# Qwiic_GPS-TwoSided.net
KiCad netlist of a schematic drawn in EAGLE
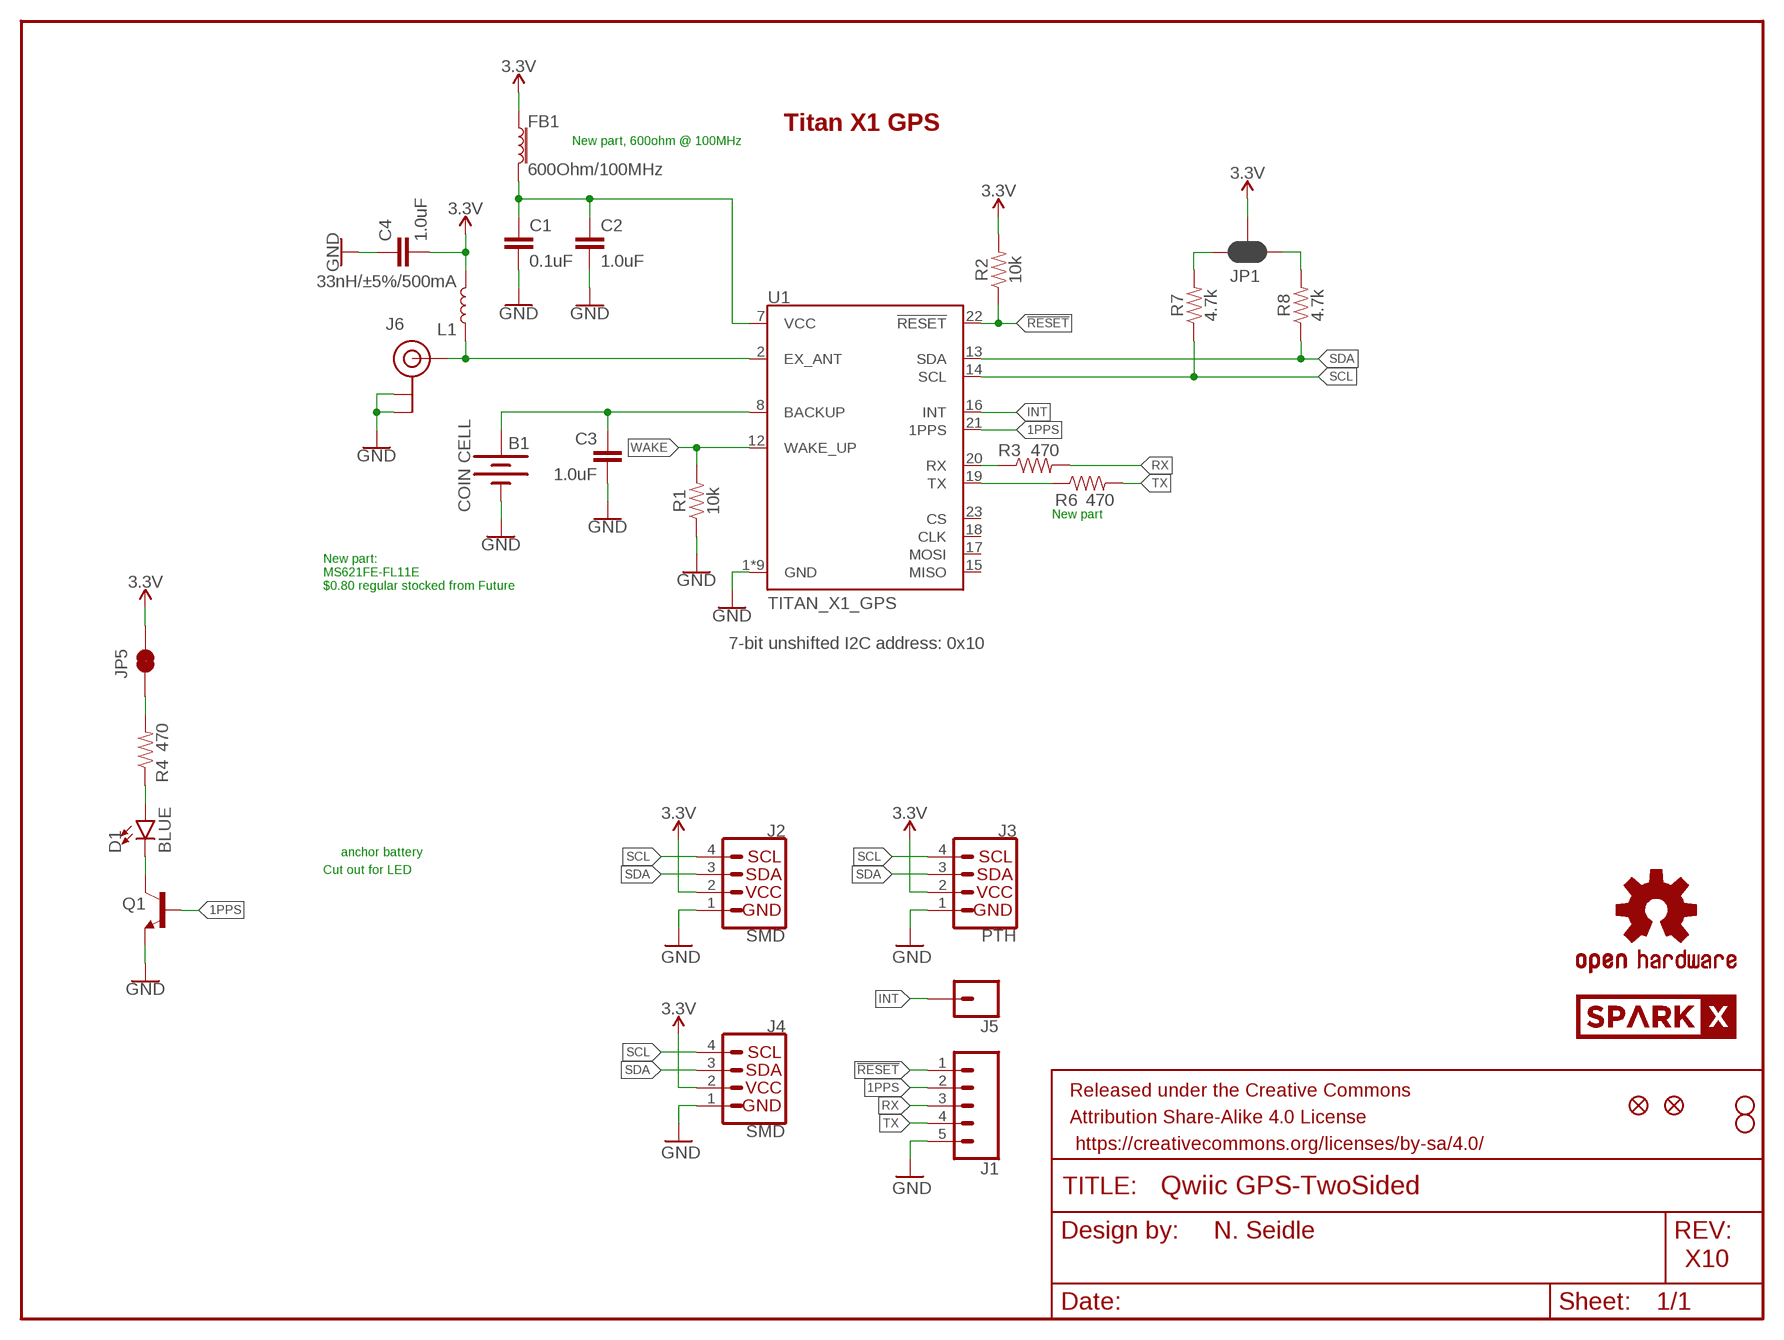
[diagram p0: schematic, sheet 1]

(export (version "E")
  (design (tool "Eeschema 10.0.6"))
  (components
    (comp (ref "B1")
      (value "COIN CELL")
      (footprint "eagle-import:6.8MM_COIN_CELL")
      (libsource (lib "eagle-import") (part "6.8MM_COIN_CELL"))
    )
    (comp (ref "C1")
      (value "0.1uF")
      (footprint "eagle-import:0603")
      (libsource (lib "eagle-import") (part "0.1UF-0603-25V-(+80/-20%)"))
    )
    (comp (ref "C2")
      (value "1.0uF")
      (footprint "eagle-import:0603")
      (libsource (lib "eagle-import") (part "1.0UF-0603-16V-10%"))
    )
    (comp (ref "C3")
      (value "1.0uF")
      (footprint "eagle-import:0603")
      (libsource (lib "eagle-import") (part "1.0UF-0603-16V-10%"))
    )
    (comp (ref "C4")
      (value "1.0uF")
      (footprint "eagle-import:0603")
      (libsource (lib "eagle-import") (part "1.0UF-0603-16V-10%"))
    )
    (comp (ref "D1")
      (value "BLUE")
      (footprint "eagle-import:LED-1206-BOTTOM")
      (libsource (lib "eagle-import") (part "LED1206-BOTTOM"))
    )
    (comp (ref "FB1")
      (value "600Ohm/100MHz")
      (footprint "eagle-import:0603")
      (libsource (lib "eagle-import") (part "FERRITE_BEAD-0603"))
    )
    (comp (ref "FRAME1")
      (value "FRAME-LETTER")
      (footprint "eagle-import:CREATIVE_COMMONS")
      (libsource (lib "eagle-import") (part "FRAME-LETTER"))
    )
    (comp (ref "J1")
      (value "CONN_05NO_SILK")
      (footprint "eagle-import:1X05_NO_SILK")
      (libsource (lib "eagle-import") (part "CONN_05NO_SILK"))
    )
    (comp (ref "J2")
      (value "SMD")
      (footprint "eagle-import:1X04_1MM_RA")
      (libsource (lib "eagle-import") (part "I2C_STANDARDJS-1MM"))
    )
    (comp (ref "J3")
      (value "PTH")
      (footprint "eagle-import:1X04_NO_SILK")
      (libsource (lib "eagle-import") (part "I2C_STANDARD_NO_SILK"))
    )
    (comp (ref "J4")
      (value "SMD")
      (footprint "eagle-import:1X04_1MM_RA")
      (libsource (lib "eagle-import") (part "I2C_STANDARDJS-1MM"))
    )
    (comp (ref "J5")
      (value "CONN_01PTH_NO_SILK_YES_STOP")
      (footprint "eagle-import:1X01_NO_SILK")
      (libsource (lib "eagle-import") (part "CONN_01PTH_NO_SILK_YES_STOP"))
    )
    (comp (ref "J6")
      (value "U.FL")
      (footprint "eagle-import:U.FL")
      (libsource (lib "eagle-import") (part "U.FL"))
    )
    (comp (ref "JP1")
      (value "JUMPER-SMT_3_2-NC_PASTE_SILK")
      (footprint "eagle-import:SMT-JUMPER_3_2-NC_PASTE_SILK")
      (libsource (lib "eagle-import") (part "JUMPER-SMT_3_2-NC_PASTE_SILK"))
    )
    (comp (ref "JP2")
      (value "FIDUCIALUFIDUCIAL")
      (footprint "eagle-import:MICRO-FIDUCIAL")
      (libsource (lib "eagle-import") (part "FIDUCIALUFIDUCIAL"))
    )
    (comp (ref "JP3")
      (value "STAND-OFF")
      (footprint "eagle-import:STAND-OFF")
      (libsource (lib "eagle-import") (part "STAND-OFF"))
    )
    (comp (ref "JP4")
      (value "STAND-OFF")
      (footprint "eagle-import:STAND-OFF")
      (libsource (lib "eagle-import") (part "STAND-OFF"))
    )
    (comp (ref "JP5")
      (value "JUMPER-SMT_2_NC_TRACE_NO-SILK")
      (footprint "eagle-import:SMT-JUMPER_2_NC_TRACE_NO-SILK")
      (libsource (lib "eagle-import") (part "JUMPER-SMT_2_NC_TRACE_NO-SILK"))
    )
    (comp (ref "JP6")
      (value "FIDUCIALUFIDUCIAL")
      (footprint "eagle-import:MICRO-FIDUCIAL")
      (libsource (lib "eagle-import") (part "FIDUCIALUFIDUCIAL"))
    )
    (comp (ref "L1")
      (value "33nH/±5%/500mA")
      (footprint "eagle-import:0603")
      (libsource (lib "eagle-import") (part "INDUCTOR-0603-33NH"))
    )
    (comp (ref "LOGO1")
      (value "OSHW-LOGOMINI")
      (footprint "eagle-import:OSHW-LOGO-MINI")
      (libsource (lib "eagle-import") (part "OSHW-LOGOMINI"))
    )
    (comp (ref "Q1")
      (value "TRANS_NPN-MMBT2222AL")
      (footprint "eagle-import:SOT23-3")
      (libsource (lib "eagle-import") (part "TRANS_NPN-MMBT2222AL"))
    )
    (comp (ref "R1")
      (value "10k")
      (footprint "eagle-import:0603")
      (libsource (lib "eagle-import") (part "10KOHM-0603-1/10W-1%"))
    )
    (comp (ref "R2")
      (value "10k")
      (footprint "eagle-import:0603")
      (libsource (lib "eagle-import") (part "10KOHM-0603-1/10W-1%"))
    )
    (comp (ref "R3")
      (value "470")
      (footprint "eagle-import:0603")
      (libsource (lib "eagle-import") (part "470OHM-0603-1/10W-1%"))
    )
    (comp (ref "R4")
      (value "470")
      (footprint "eagle-import:0603")
      (libsource (lib "eagle-import") (part "470OHM-0603-1/10W-1%"))
    )
    (comp (ref "R6")
      (value "470")
      (footprint "eagle-import:0603")
      (libsource (lib "eagle-import") (part "470OHM-0603-1/10W-1%"))
    )
    (comp (ref "R7")
      (value "4.7k")
      (footprint "eagle-import:0603")
      (libsource (lib "eagle-import") (part "4.7KOHM-0603-1/10W-1%"))
    )
    (comp (ref "R8")
      (value "4.7k")
      (footprint "eagle-import:0603")
      (libsource (lib "eagle-import") (part "4.7KOHM-0603-1/10W-1%"))
    )
    (comp (ref "U$1")
      (value "SPARKX-LOGO4")
      (footprint "eagle-import:SPARKX-MEDIUM")
      (libsource (lib "eagle-import") (part "SPARKX-LOGO4"))
    )
    (comp (ref "U$2")
      (value "SPARKX-LOGO4")
      (footprint "eagle-import:SPARKX-MEDIUM")
      (libsource (lib "eagle-import") (part "SPARKX-LOGO4"))
    )
    (comp (ref "U1")
      (value "TITAN_X1_GPS")
      (footprint "eagle-import:TITAN_X1_GPS")
      (libsource (lib "eagle-import") (part "TITAN_X1_GPS"))
    )
  )
  (nets
    (net (code "1") (name "/~{RESET}") (class "Default")
      (node (ref "J1") (pin "1") (pinfunction "1_1") (pintype "passive"))
      (node (ref "R2") (pin "1") (pinfunction "1_1") (pintype "passive"))
      (node (ref "U1") (pin "22") (pinfunction "~{RESET}_22") (pintype "bidirectional"))
    )
    (net (code "2") (name "1PPS") (class "Default")
      (node (ref "J1") (pin "2") (pinfunction "2_2") (pintype "passive"))
      (node (ref "Q1") (pin "1") (pinfunction "B_1") (pintype "passive"))
      (node (ref "U1") (pin "21") (pinfunction "1PPS_21") (pintype "bidirectional"))
    )
    (net (code "3") (name "3.3V") (class "Default")
      (node (ref "C4") (pin "2") (pinfunction "2_2") (pintype "passive"))
      (node (ref "FB1") (pin "1") (pinfunction "1_1") (pintype "passive"))
      (node (ref "J2") (pin "2") (pinfunction "VCC_2") (pintype "power_in"))
      (node (ref "J3") (pin "2") (pinfunction "VCC_2") (pintype "power_in"))
      (node (ref "J4") (pin "2") (pinfunction "VCC_2") (pintype "power_in"))
      (node (ref "JP1") (pin "2") (pinfunction "2_2") (pintype "passive"))
      (node (ref "JP5") (pin "2") (pinfunction "2_2") (pintype "passive"))
      (node (ref "L1") (pin "2") (pinfunction "2_2") (pintype "passive"))
      (node (ref "R2") (pin "2") (pinfunction "2_2") (pintype "passive"))
    )
    (net (code "4") (name "GND") (class "Default")
      (node (ref "B1") (pin "-") (pinfunction "-_-") (pintype "power_in"))
      (node (ref "C1") (pin "2") (pinfunction "2_2") (pintype "passive"))
      (node (ref "C2") (pin "2") (pinfunction "2_2") (pintype "passive"))
      (node (ref "C3") (pin "2") (pinfunction "2_2") (pintype "passive"))
      (node (ref "C4") (pin "1") (pinfunction "1_1") (pintype "passive"))
      (node (ref "J1") (pin "5") (pinfunction "5_5") (pintype "passive"))
      (node (ref "J2") (pin "1") (pinfunction "GND_1") (pintype "power_in"))
      (node (ref "J3") (pin "1") (pinfunction "GND_1") (pintype "power_in"))
      (node (ref "J4") (pin "1") (pinfunction "GND_1") (pintype "power_in"))
      (node (ref "J6") (pin "P$1") (pinfunction "GND_P$1") (pintype "bidirectional"))
      (node (ref "J6") (pin "P$2") (pinfunction "GND_P$2") (pintype "bidirectional"))
      (node (ref "Q1") (pin "2") (pinfunction "E_2") (pintype "passive"))
      (node (ref "R1") (pin "1") (pinfunction "1_1") (pintype "passive"))
      (node (ref "U1") (pin "1") (pinfunction "GND_1") (pintype "bidirectional"))
      (node (ref "U1") (pin "10") (pinfunction "GND_10") (pintype "bidirectional"))
      (node (ref "U1") (pin "11") (pinfunction "GND_11") (pintype "bidirectional"))
      (node (ref "U1") (pin "24") (pinfunction "GND_24") (pintype "bidirectional"))
      (node (ref "U1") (pin "3") (pinfunction "GND_3") (pintype "bidirectional"))
      (node (ref "U1") (pin "4") (pinfunction "GND_4") (pintype "bidirectional"))
      (node (ref "U1") (pin "5") (pinfunction "GND_5") (pintype "bidirectional"))
      (node (ref "U1") (pin "6") (pinfunction "GND_6") (pintype "bidirectional"))
      (node (ref "U1") (pin "9") (pinfunction "GND_9") (pintype "bidirectional"))
    )
    (net (code "5") (name "INT") (class "Default")
      (node (ref "J5") (pin "1") (pinfunction "1_1") (pintype "passive"))
      (node (ref "U1") (pin "16") (pinfunction "INT_16") (pintype "bidirectional"))
    )
    (net (code "6") (name "Net-(D1-PadA)") (class "Default")
      (node (ref "D1") (pin "A") (pinfunction "A_A") (pintype "passive"))
      (node (ref "R4") (pin "1") (pinfunction "1_1") (pintype "passive"))
    )
    (net (code "7") (name "Net-(J6-SIGNAL)") (class "Default")
      (node (ref "J6") (pin "P$3") (pinfunction "SIGNAL_P$3") (pintype "bidirectional"))
      (node (ref "L1") (pin "1") (pinfunction "1_1") (pintype "passive"))
      (node (ref "U1") (pin "2") (pinfunction "EX_ANT_2") (pintype "bidirectional"))
    )
    (net (code "8") (name "Net-(JP1-Pad1)") (class "Default")
      (node (ref "JP1") (pin "1") (pinfunction "1_1") (pintype "passive"))
      (node (ref "R8") (pin "2") (pinfunction "2_2") (pintype "passive"))
    )
    (net (code "9") (name "Net-(JP1-Pad3)") (class "Default")
      (node (ref "JP1") (pin "3") (pinfunction "3_3") (pintype "passive"))
      (node (ref "R7") (pin "2") (pinfunction "2_2") (pintype "passive"))
    )
    (net (code "10") (name "Net-(JP5-Pad1)") (class "Default")
      (node (ref "JP5") (pin "1") (pinfunction "1_1") (pintype "passive"))
      (node (ref "R4") (pin "2") (pinfunction "2_2") (pintype "passive"))
    )
    (net (code "11") (name "Net-(Q1-C)") (class "Default")
      (node (ref "D1") (pin "C") (pinfunction "C_C") (pintype "passive"))
      (node (ref "Q1") (pin "3") (pinfunction "C_3") (pintype "passive"))
    )
    (net (code "12") (name "Net-(U1-BACKUP)") (class "Default")
      (node (ref "B1") (pin "+") (pinfunction "+_+") (pintype "power_in"))
      (node (ref "C3") (pin "1") (pinfunction "1_1") (pintype "passive"))
      (node (ref "U1") (pin "8") (pinfunction "BACKUP_8") (pintype "bidirectional"))
    )
    (net (code "13") (name "Net-(U1-RX)") (class "Default")
      (node (ref "R3") (pin "1") (pinfunction "1_1") (pintype "passive"))
      (node (ref "U1") (pin "20") (pinfunction "RX_20") (pintype "bidirectional"))
    )
    (net (code "14") (name "Net-(U1-TX)") (class "Default")
      (node (ref "R6") (pin "1") (pinfunction "1_1") (pintype "passive"))
      (node (ref "U1") (pin "19") (pinfunction "TX_19") (pintype "bidirectional"))
    )
    (net (code "15") (name "Net-(U1-VCC)") (class "Default")
      (node (ref "C1") (pin "1") (pinfunction "1_1") (pintype "passive"))
      (node (ref "C2") (pin "1") (pinfunction "1_1") (pintype "passive"))
      (node (ref "FB1") (pin "2") (pinfunction "2_2") (pintype "passive"))
      (node (ref "U1") (pin "7") (pinfunction "VCC_7") (pintype "bidirectional"))
    )
    (net (code "16") (name "RX") (class "Default")
      (node (ref "J1") (pin "3") (pinfunction "3_3") (pintype "passive"))
      (node (ref "R3") (pin "2") (pinfunction "2_2") (pintype "passive"))
    )
    (net (code "17") (name "SCL") (class "Default")
      (node (ref "J2") (pin "4") (pinfunction "SCL_4") (pintype "passive"))
      (node (ref "J3") (pin "4") (pinfunction "SCL_4") (pintype "passive"))
      (node (ref "J4") (pin "4") (pinfunction "SCL_4") (pintype "passive"))
      (node (ref "R7") (pin "1") (pinfunction "1_1") (pintype "passive"))
      (node (ref "U1") (pin "14") (pinfunction "SCL_14") (pintype "bidirectional"))
    )
    (net (code "18") (name "SDA") (class "Default")
      (node (ref "J2") (pin "3") (pinfunction "SDA_3") (pintype "passive"))
      (node (ref "J3") (pin "3") (pinfunction "SDA_3") (pintype "passive"))
      (node (ref "J4") (pin "3") (pinfunction "SDA_3") (pintype "passive"))
      (node (ref "R8") (pin "1") (pinfunction "1_1") (pintype "passive"))
      (node (ref "U1") (pin "13") (pinfunction "SDA_13") (pintype "bidirectional"))
    )
    (net (code "19") (name "TX") (class "Default")
      (node (ref "J1") (pin "4") (pinfunction "4_4") (pintype "passive"))
      (node (ref "R6") (pin "2") (pinfunction "2_2") (pintype "passive"))
    )
    (net (code "20") (name "WAKE") (class "Default")
      (node (ref "R1") (pin "2") (pinfunction "2_2") (pintype "passive"))
      (node (ref "U1") (pin "12") (pinfunction "WAKE_UP_12") (pintype "bidirectional"))
    )
    (net (code "21") (name "unconnected-(U1-CLK-Pad18)") (class "Default")
      (node (ref "U1") (pin "18") (pinfunction "CLK_18") (pintype "bidirectional"))
    )
    (net (code "22") (name "unconnected-(U1-CS-Pad23)") (class "Default")
      (node (ref "U1") (pin "23") (pinfunction "CS_23") (pintype "bidirectional"))
    )
    (net (code "23") (name "unconnected-(U1-MISO-Pad15)") (class "Default")
      (node (ref "U1") (pin "15") (pinfunction "MISO_15") (pintype "bidirectional"))
    )
    (net (code "24") (name "unconnected-(U1-MOSI-Pad17)") (class "Default")
      (node (ref "U1") (pin "17") (pinfunction "MOSI_17") (pintype "bidirectional"))
    )
  )
)
